# RXX-QDSB-SCH11-V1_00.net
KiCad netlist of a schematic drawn in Altium Designer
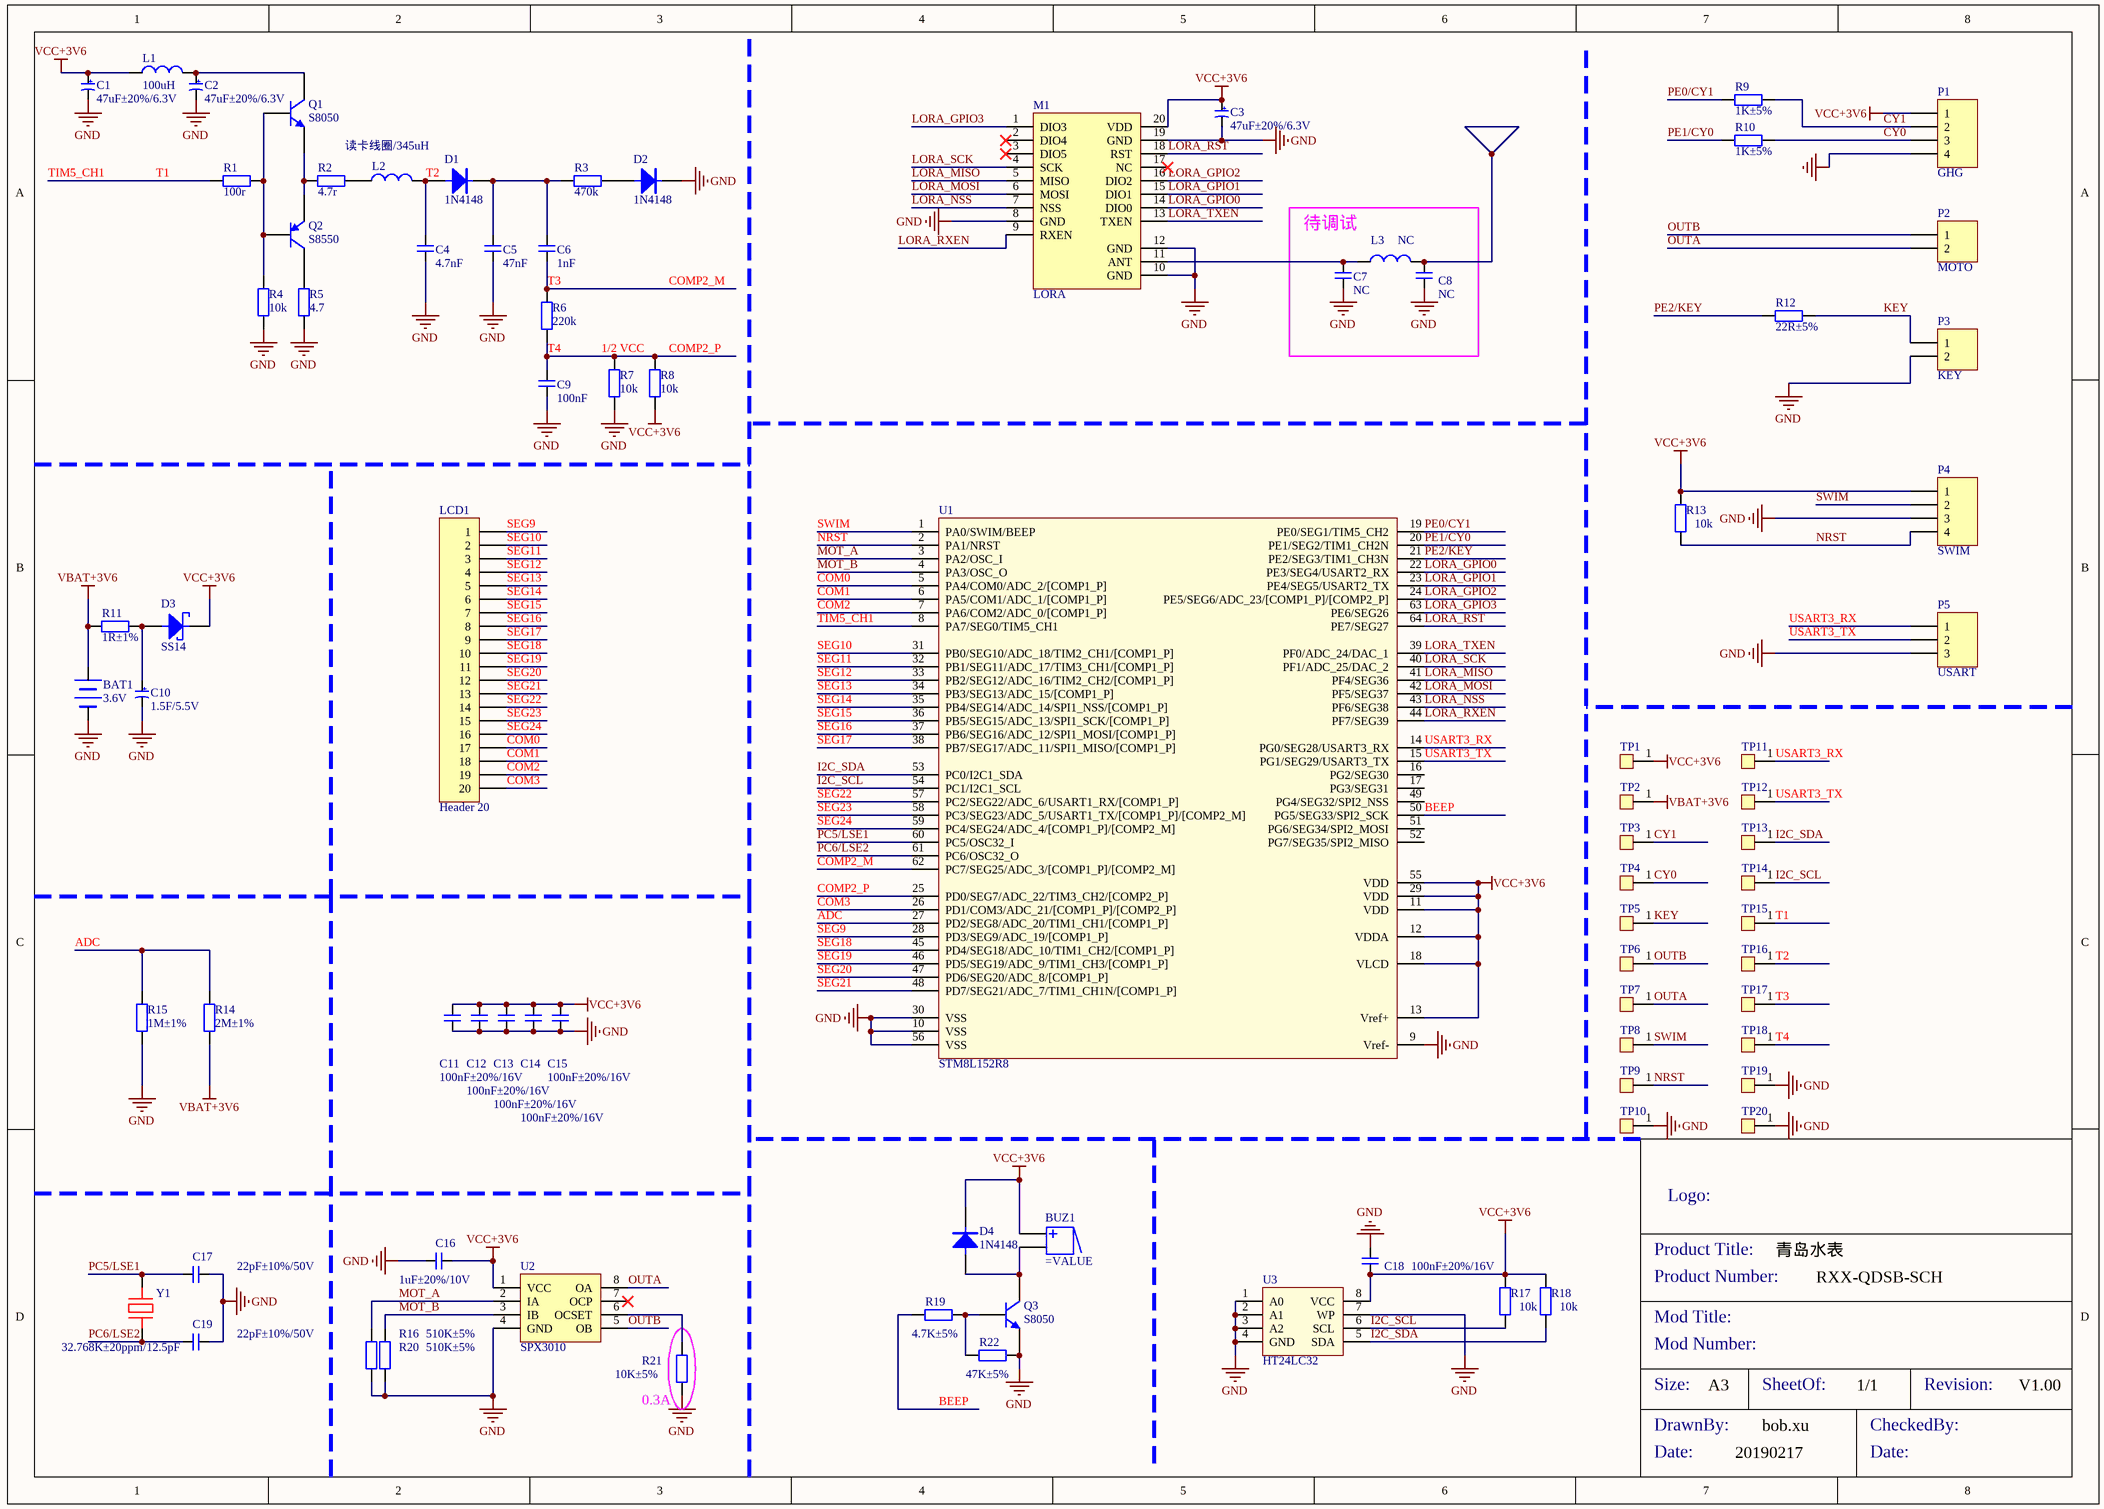
[diagram p0: RXX-QDSB-SCH11-V1.00.SchDoc]

(export (version "E")
  (design (tool "Eeschema 10.0.6"))
  (components
    (comp (ref "BAT1") (value "3.6V") (footprint "PH_2P_2R0_5R0X6R0_A") (libsource (lib "瑞臻信息") (part "BAT")))
    (comp (ref "BUZ1")
      (value "~")
      (footprint "DIP_BUZZER_2P_6R5_D12H9")
      (libsource (lib "瑞臻信息") (part "有源蜂鸣器"))
    )
    (comp (ref "C1")
      (value "47uF±20%/6.3V")
      (footprint "C3216+")
      (description "极性电容")
      (libsource (lib "瑞臻信息") (part "极性电容"))
    )
    (comp (ref "C2")
      (value "47uF±20%/6.3V")
      (footprint "C3216+")
      (description "极性电容")
      (libsource (lib "瑞臻信息") (part "极性电容"))
    )
    (comp (ref "C3")
      (value "47uF±20%/6.3V")
      (footprint "C3216+")
      (description "极性电容")
      (libsource (lib "瑞臻信息") (part "极性电容"))
    )
    (comp (ref "C4") (value "4.7nF") (description "无极性电容") (libsource (lib "瑞臻信息") (part "无极性电容")))
    (comp (ref "C5") (value "47nF") (description "无极性电容") (libsource (lib "瑞臻信息") (part "无极性电容")))
    (comp (ref "C6") (value "1nF") (description "无极性电容") (libsource (lib "瑞臻信息") (part "无极性电容")))
    (comp (ref "C7")
      (value "NC")
      (footprint "C0402")
      (description "无极性电容")
      (libsource (lib "瑞臻信息") (part "无极性电容"))
    )
    (comp (ref "C8")
      (value "NC")
      (footprint "C0402")
      (description "无极性电容")
      (libsource (lib "瑞臻信息") (part "无极性电容"))
    )
    (comp (ref "C9") (value "100nF") (description "无极性电容") (libsource (lib "瑞臻信息") (part "无极性电容")))
    (comp (ref "C10")
      (value "1.5F/5.5V")
      (footprint "CAP_2P_11R0_20X25H10_W")
      (description "极性电容")
      (libsource (lib "瑞臻信息") (part "极性电容"))
    )
    (comp (ref "C11")
      (value "100nF±20%/16V")
      (footprint "C0402")
      (description "无极性电容")
      (libsource (lib "瑞臻信息") (part "无极性电容"))
    )
    (comp (ref "C12")
      (value "100nF±20%/16V")
      (footprint "C0402")
      (description "无极性电容")
      (libsource (lib "瑞臻信息") (part "无极性电容"))
    )
    (comp (ref "C13")
      (value "100nF±20%/16V")
      (footprint "C0402")
      (description "无极性电容")
      (libsource (lib "瑞臻信息") (part "无极性电容"))
    )
    (comp (ref "C14")
      (value "100nF±20%/16V")
      (footprint "C0402")
      (description "无极性电容")
      (libsource (lib "瑞臻信息") (part "无极性电容"))
    )
    (comp (ref "C15")
      (value "100nF±20%/16V")
      (footprint "C0402")
      (description "无极性电容")
      (libsource (lib "瑞臻信息") (part "无极性电容"))
    )
    (comp (ref "C16")
      (value "1uF±20%/10V")
      (footprint "C0402")
      (description "无极性电容")
      (libsource (lib "瑞臻信息") (part "无极性电容"))
    )
    (comp (ref "C17")
      (value "22pF±10%/50V")
      (footprint "C0402")
      (description "无极性电容")
      (libsource (lib "瑞臻信息") (part "无极性电容"))
    )
    (comp (ref "C18")
      (value "100nF±20%/16V")
      (footprint "C0402")
      (description "无极性电容")
      (libsource (lib "瑞臻信息") (part "无极性电容"))
    )
    (comp (ref "C19")
      (value "22pF±10%/50V")
      (footprint "C0402")
      (description "无极性电容")
      (libsource (lib "瑞臻信息") (part "无极性电容"))
    )
    (comp (ref "D1") (value "1N4148") (description "普通二极管") (libsource (lib "瑞臻信息") (part "普通二极管")))
    (comp (ref "D2") (value "1N4148") (description "普通二极管") (libsource (lib "瑞臻信息") (part "普通二极管")))
    (comp (ref "D3")
      (value "SS14")
      (footprint "SMA_2P_2R8X4R6")
      (description "肖特基二极管")
      (libsource (lib "瑞臻信息") (part "肖特基二极管"))
    )
    (comp (ref "D4") (value "1N4148") (description "普通二极管") (libsource (lib "瑞臻信息") (part "普通二极管")))
    (comp (ref "L1") (value "100uH") (description "普通电感") (libsource (lib "瑞臻信息") (part "普通电感")))
    (comp (ref "L2") (value "读卡线圈/345uH") (description "普通电感") (libsource (lib "瑞臻信息") (part "普通电感")))
    (comp (ref "L3")
      (value "NC")
      (footprint "L0402")
      (description "普通电感")
      (libsource (lib "瑞臻信息") (part "普通电感"))
    )
    (comp (ref "LCD1")
      (value "Header 20")
      (footprint "HDR1X20")
      (description "Header, 20-Pin")
      (fields (field (name "PUBLISHER") "Altium Limited"))
      (libsource (lib "Miscellaneous Connectors") (part "Header 20"))
    )
    (comp (ref "M1") (value "LORA") (footprint "LORA_PIN_1") (libsource (lib "瑞臻信息") (part "LORA_PIN_1")))
    (comp (ref "P1")
      (value "GHG")
      (footprint "PH_4P_2R0_5R0X10R0_A")
      (description "Header, 4-Pin")
      (fields (field (name "PUBLISHER") "Altium Limited"))
      (libsource (lib "Miscellaneous Connectors") (part "Header 4"))
    )
    (comp (ref "P2")
      (value "MOTO")
      (footprint "PH_2P_2R0_5R0X6R0_A")
      (description "Header, 2-Pin")
      (fields (field (name "PUBLISHER") "Altium Limited"))
      (libsource (lib "Miscellaneous Connectors") (part "Header 2"))
    )
    (comp (ref "P3")
      (value "KEY")
      (footprint "PH_2P_2R0_5R0X6R0_A")
      (description "Header, 2-Pin")
      (fields (field (name "PUBLISHER") "Altium Limited"))
      (libsource (lib "Miscellaneous Connectors") (part "Header 2"))
    )
    (comp (ref "P4")
      (value "SWIM")
      (footprint "PH_4P_2R0_5R0X10R0_A")
      (description "Header, 4-Pin")
      (fields (field (name "PUBLISHER") "Altium Limited"))
      (libsource (lib "Miscellaneous Connectors") (part "Header 4"))
    )
    (comp (ref "P5")
      (value "USART")
      (footprint "PH_3P_2R0_5R0X8R0_A")
      (description "Header, 3-Pin")
      (fields (field (name "PUBLISHER") "Altium Limited"))
      (libsource (lib "Miscellaneous Connectors") (part "Header 3"))
    )
    (comp (ref "Q1") (value "S8050") (description "NPN三极管") (libsource (lib "瑞臻信息") (part "NPN三极管")))
    (comp (ref "Q2") (value "S8550") (description "PNP三极管") (libsource (lib "瑞臻信息") (part "PNP三极管")))
    (comp (ref "Q3")
      (value "S8050")
      (footprint "SOT23_3P_0R95_1R3X2R9")
      (description "NPN三极管")
      (libsource (lib "瑞臻信息") (part "NPN三极管"))
    )
    (comp (ref "R1") (value "100r") (description "普通电阻") (libsource (lib "") (part "普通电阻_3")))
    (comp (ref "R2") (value "4.7r") (description "普通电阻") (libsource (lib "") (part "普通电阻_3")))
    (comp (ref "R3") (value "470k") (description "普通电阻") (libsource (lib "") (part "普通电阻_3")))
    (comp (ref "R4") (value "10k") (description "普通电阻") (libsource (lib "") (part "普通电阻_2")))
    (comp (ref "R5") (value "4.7") (description "普通电阻") (libsource (lib "") (part "普通电阻_2")))
    (comp (ref "R6") (value "220k") (description "普通电阻") (libsource (lib "") (part "普通电阻_1")))
    (comp (ref "R7") (value "10k") (description "普通电阻") (libsource (lib "") (part "普通电阻_1")))
    (comp (ref "R8") (value "10k") (description "普通电阻") (libsource (lib "") (part "普通电阻_1")))
    (comp (ref "R9")
      (value "1K±5%")
      (footprint "R0402")
      (description "普通电阻")
      (libsource (lib "") (part "普通电阻_3"))
    )
    (comp (ref "R10")
      (value "1K±5%")
      (footprint "R0402")
      (description "普通电阻")
      (libsource (lib "") (part "普通电阻_3"))
    )
    (comp (ref "R11")
      (value "1R±1%")
      (footprint "R0805")
      (description "普通电阻")
      (libsource (lib "瑞臻信息") (part "普通电阻"))
    )
    (comp (ref "R12")
      (value "22R±5%")
      (footprint "R0402")
      (description "普通电阻")
      (libsource (lib "") (part "普通电阻_3"))
    )
    (comp (ref "R13")
      (value "10k")
      (footprint "R0402")
      (description "普通电阻")
      (libsource (lib "") (part "普通电阻_2"))
    )
    (comp (ref "R14")
      (value "2M±1%")
      (footprint "R0402")
      (description "普通电阻")
      (libsource (lib "") (part "普通电阻_1"))
    )
    (comp (ref "R15")
      (value "1M±1%")
      (footprint "R0402")
      (description "普通电阻")
      (libsource (lib "") (part "普通电阻_2"))
    )
    (comp (ref "R16")
      (value "510K±5%")
      (footprint "R0402")
      (description "普通电阻")
      (libsource (lib "") (part "普通电阻_2"))
    )
    (comp (ref "R17")
      (value "10k")
      (footprint "R0402")
      (description "普通电阻")
      (libsource (lib "") (part "普通电阻_2"))
    )
    (comp (ref "R18")
      (value "10k")
      (footprint "R0402")
      (description "普通电阻")
      (libsource (lib "") (part "普通电阻_2"))
    )
    (comp (ref "R19")
      (value "4.7K±5%")
      (footprint "R0402")
      (description "普通电阻")
      (libsource (lib "") (part "普通电阻_3"))
    )
    (comp (ref "R20")
      (value "510K±5%")
      (footprint "R0402")
      (description "普通电阻")
      (libsource (lib "") (part "普通电阻_2"))
    )
    (comp (ref "R21")
      (value "10K±5%")
      (footprint "R0402")
      (description "普通电阻")
      (libsource (lib "") (part "普通电阻_2"))
    )
    (comp (ref "R22")
      (value "47K±5%")
      (footprint "R0402")
      (description "普通电阻")
      (libsource (lib "瑞臻信息") (part "普通电阻"))
    )
    (comp (ref "TP1") (value "~") (description "测试点") (libsource (lib "瑞臻信息") (part "Test_Point")))
    (comp (ref "TP2") (value "~") (description "测试点") (libsource (lib "瑞臻信息") (part "Test_Point")))
    (comp (ref "TP3") (value "~") (description "测试点") (libsource (lib "瑞臻信息") (part "Test_Point")))
    (comp (ref "TP4") (value "~") (description "测试点") (libsource (lib "瑞臻信息") (part "Test_Point")))
    (comp (ref "TP5") (value "~") (description "测试点") (libsource (lib "瑞臻信息") (part "Test_Point")))
    (comp (ref "TP6") (value "~") (description "测试点") (libsource (lib "瑞臻信息") (part "Test_Point")))
    (comp (ref "TP7") (value "~") (description "测试点") (libsource (lib "瑞臻信息") (part "Test_Point")))
    (comp (ref "TP8") (value "~") (description "测试点") (libsource (lib "瑞臻信息") (part "Test_Point")))
    (comp (ref "TP9") (value "~") (description "测试点") (libsource (lib "瑞臻信息") (part "Test_Point")))
    (comp (ref "TP10") (value "~") (description "测试点") (libsource (lib "瑞臻信息") (part "Test_Point")))
    (comp (ref "TP11") (value "~") (description "测试点") (libsource (lib "瑞臻信息") (part "Test_Point")))
    (comp (ref "TP12") (value "~") (description "测试点") (libsource (lib "瑞臻信息") (part "Test_Point")))
    (comp (ref "TP13") (value "~") (description "测试点") (libsource (lib "瑞臻信息") (part "Test_Point")))
    (comp (ref "TP14") (value "~") (description "测试点") (libsource (lib "瑞臻信息") (part "Test_Point")))
    (comp (ref "TP15") (value "~") (description "测试点") (libsource (lib "瑞臻信息") (part "Test_Point")))
    (comp (ref "TP16") (value "~") (description "测试点") (libsource (lib "瑞臻信息") (part "Test_Point")))
    (comp (ref "TP17") (value "~") (description "测试点") (libsource (lib "瑞臻信息") (part "Test_Point")))
    (comp (ref "TP18") (value "~") (description "测试点") (libsource (lib "瑞臻信息") (part "Test_Point")))
    (comp (ref "TP19") (value "~") (description "测试点") (libsource (lib "瑞臻信息") (part "Test_Point")))
    (comp (ref "TP20") (value "~") (description "测试点") (libsource (lib "瑞臻信息") (part "Test_Point")))
    (comp (ref "U1") (value "STM8L152R8") (libsource (lib "瑞臻信息") (part "STM8L152R8")))
    (comp (ref "U2")
      (value "SPX3010")
      (footprint "SOP_8P_1R27_3R9X4R9")
      (libsource (lib "瑞臻信息") (part "SPX3010"))
    )
    (comp (ref "U3")
      (value "HT24LC32")
      (footprint "SOP_8P_1R27_3R9X4R9")
      (libsource (lib "瑞臻信息") (part "24CXX"))
    )
    (comp (ref "Y1")
      (value "32.768K±20ppm/12.5pF")
      (footprint "SMD_Crystal_2P_1R5X3R2")
      (description "两脚晶体谐振器")
      (libsource (lib "瑞臻信息") (part "两脚晶体谐振器"))
    )
  )
  (nets
    (net (code "1") (name "/1{slash}2 VCC") (class "Default")
      (node (ref "C9") (pin "1") (pinfunction "1_1") (pintype "passive"))
      (node (ref "R6") (pin "2") (pinfunction "2_2") (pintype "passive"))
      (node (ref "R7") (pin "1") (pinfunction "1_1") (pintype "passive"))
      (node (ref "R8") (pin "1") (pinfunction "1_1") (pintype "passive"))
      (node (ref "TP18") (pin "1") (pinfunction "1_1") (pintype "passive"))
      (node (ref "U1") (pin "25") (pinfunction "PD0/SEG7/ADC_22/TIM3_CH2/[COMP2_P]_25") (pintype "passive"))
    )
    (net (code "2") (name "/ADC") (class "Default")
      (node (ref "R14") (pin "1") (pinfunction "1_1") (pintype "passive"))
      (node (ref "R15") (pin "2") (pinfunction "2_2") (pintype "passive"))
      (node (ref "U1") (pin "27") (pinfunction "PD2/SEG8/ADC_20/TIM1_CH1/[COMP1_P]_27") (pintype "passive"))
    )
    (net (code "3") (name "/BEEP") (class "Default")
      (node (ref "R19") (pin "2") (pinfunction "2_2") (pintype "passive"))
      (node (ref "U1") (pin "50") (pinfunction "PG5/SEG33/SPI2_SCK_50") (pintype "passive"))
    )
    (net (code "4") (name "/COM0") (class "Default")
      (node (ref "LCD1") (pin "17") (pinfunction "17_17") (pintype "passive"))
      (node (ref "U1") (pin "5") (pinfunction "PA4/COM0/ADC_2/[COMP1_P]_5") (pintype "passive"))
    )
    (net (code "5") (name "/COM1") (class "Default")
      (node (ref "LCD1") (pin "18") (pinfunction "18_18") (pintype "passive"))
      (node (ref "U1") (pin "6") (pinfunction "PA5/COM1/ADC_1/[COMP1_P]_6") (pintype "passive"))
    )
    (net (code "6") (name "/COM2") (class "Default")
      (node (ref "LCD1") (pin "19") (pinfunction "19_19") (pintype "passive"))
      (node (ref "U1") (pin "7") (pinfunction "PA6/COM2/ADC_0/[COMP1_P]_7") (pintype "passive"))
    )
    (net (code "7") (name "/COM3") (class "Default")
      (node (ref "LCD1") (pin "20") (pinfunction "20_20") (pintype "passive"))
      (node (ref "U1") (pin "26") (pinfunction "PD1/COM3/ADC_21/[COMP1_P]/[COMP2_P]_26") (pintype "passive"))
    )
    (net (code "8") (name "/COMP2_M") (class "Default")
      (node (ref "C6") (pin "2") (pinfunction "2_2") (pintype "passive"))
      (node (ref "R6") (pin "1") (pinfunction "1_1") (pintype "passive"))
      (node (ref "TP17") (pin "1") (pinfunction "1_1") (pintype "passive"))
      (node (ref "U1") (pin "62") (pinfunction "PC7/SEG25/ADC_3/[COMP1_P]/[COMP2_M]_62") (pintype "passive"))
    )
    (net (code "9") (name "/CY0") (class "Default")
      (node (ref "P1") (pin "3") (pinfunction "3_3") (pintype "passive"))
      (node (ref "R10") (pin "1") (pinfunction "1_1") (pintype "passive"))
      (node (ref "TP4") (pin "1") (pinfunction "1_1") (pintype "passive"))
    )
    (net (code "10") (name "/CY1") (class "Default")
      (node (ref "P1") (pin "2") (pinfunction "2_2") (pintype "passive"))
      (node (ref "R9") (pin "1") (pinfunction "1_1") (pintype "passive"))
      (node (ref "TP3") (pin "1") (pinfunction "1_1") (pintype "passive"))
    )
    (net (code "11") (name "/I2C_SCL") (class "Default")
      (node (ref "R17") (pin "1") (pinfunction "1_1") (pintype "passive"))
      (node (ref "TP14") (pin "1") (pinfunction "1_1") (pintype "passive"))
      (node (ref "U1") (pin "54") (pinfunction "PC1/I2C1_SCL_54") (pintype "passive"))
      (node (ref "U3") (pin "6") (pinfunction "SCL_6") (pintype "passive"))
    )
    (net (code "12") (name "/I2C_SDA") (class "Default")
      (node (ref "R18") (pin "1") (pinfunction "1_1") (pintype "passive"))
      (node (ref "TP13") (pin "1") (pinfunction "1_1") (pintype "passive"))
      (node (ref "U1") (pin "53") (pinfunction "PC0/I2C1_SDA_53") (pintype "passive"))
      (node (ref "U3") (pin "5") (pinfunction "SDA_5") (pintype "passive"))
    )
    (net (code "13") (name "/KEY") (class "Default")
      (node (ref "P3") (pin "1") (pinfunction "1_1") (pintype "passive"))
      (node (ref "R12") (pin "1") (pinfunction "1_1") (pintype "passive"))
      (node (ref "TP5") (pin "1") (pinfunction "1_1") (pintype "passive"))
    )
    (net (code "14") (name "/LORA_GPIO0") (class "Default")
      (node (ref "M1") (pin "14") (pinfunction "DIO0_14") (pintype "passive"))
      (node (ref "U1") (pin "22") (pinfunction "PE3/SEG4/USART2_RX_22") (pintype "passive"))
    )
    (net (code "15") (name "/LORA_GPIO1") (class "Default")
      (node (ref "M1") (pin "15") (pinfunction "DIO1_15") (pintype "passive"))
      (node (ref "U1") (pin "23") (pinfunction "PE4/SEG5/USART2_TX_23") (pintype "passive"))
    )
    (net (code "16") (name "/LORA_GPIO2") (class "Default")
      (node (ref "M1") (pin "16") (pinfunction "DIO2_16") (pintype "passive"))
      (node (ref "U1") (pin "24") (pinfunction "PE5/SEG6/ADC_23/[COMP1_P]/[COMP2_P]_24") (pintype "passive"))
    )
    (net (code "17") (name "/LORA_GPIO3") (class "Default")
      (node (ref "M1") (pin "1") (pinfunction "DIO3_1") (pintype "passive"))
      (node (ref "U1") (pin "63") (pinfunction "PE6/SEG26_63") (pintype "passive"))
    )
    (net (code "18") (name "/LORA_MISO") (class "Default")
      (node (ref "M1") (pin "5") (pinfunction "MISO_5") (pintype "passive"))
      (node (ref "U1") (pin "41") (pinfunction "PF4/SEG36_41") (pintype "passive"))
    )
    (net (code "19") (name "/LORA_MOSI") (class "Default")
      (node (ref "M1") (pin "6") (pinfunction "MOSI_6") (pintype "passive"))
      (node (ref "U1") (pin "42") (pinfunction "PF5/SEG37_42") (pintype "passive"))
    )
    (net (code "20") (name "/LORA_NSS") (class "Default")
      (node (ref "M1") (pin "7") (pinfunction "NSS_7") (pintype "passive"))
      (node (ref "U1") (pin "43") (pinfunction "PF6/SEG38_43") (pintype "passive"))
    )
    (net (code "21") (name "/LORA_RST") (class "Default")
      (node (ref "M1") (pin "18") (pinfunction "RST_18") (pintype "passive"))
      (node (ref "U1") (pin "64") (pinfunction "PE7/SEG27_64") (pintype "passive"))
    )
    (net (code "22") (name "/LORA_RXEN") (class "Default")
      (node (ref "M1") (pin "9") (pinfunction "RXEN_9") (pintype "passive"))
      (node (ref "U1") (pin "44") (pinfunction "PF7/SEG39_44") (pintype "passive"))
    )
    (net (code "23") (name "/LORA_SCK") (class "Default")
      (node (ref "M1") (pin "4") (pinfunction "SCK_4") (pintype "passive"))
      (node (ref "U1") (pin "40") (pinfunction "PF1/ADC_25/DAC_2_40") (pintype "passive"))
    )
    (net (code "24") (name "/LORA_TXEN") (class "Default")
      (node (ref "M1") (pin "13") (pinfunction "TXEN_13") (pintype "passive"))
      (node (ref "U1") (pin "39") (pinfunction "PF0/ADC_24/DAC_1_39") (pintype "passive"))
    )
    (net (code "25") (name "/MOT_A") (class "Default")
      (node (ref "R16") (pin "2") (pinfunction "2_2") (pintype "passive"))
      (node (ref "U1") (pin "3") (pinfunction "PA2/OSC_I_3") (pintype "passive"))
      (node (ref "U2") (pin "2") (pinfunction "IA_2") (pintype "passive"))
    )
    (net (code "26") (name "/MOT_B") (class "Default")
      (node (ref "R20") (pin "2") (pinfunction "2_2") (pintype "passive"))
      (node (ref "U1") (pin "4") (pinfunction "PA3/OSC_O_4") (pintype "passive"))
      (node (ref "U2") (pin "3") (pinfunction "IB_3") (pintype "passive"))
    )
    (net (code "27") (name "/NRST") (class "Default")
      (node (ref "P4") (pin "4") (pinfunction "4_4") (pintype "passive"))
      (node (ref "R13") (pin "1") (pinfunction "1_1") (pintype "passive"))
      (node (ref "TP9") (pin "1") (pinfunction "1_1") (pintype "passive"))
      (node (ref "U1") (pin "2") (pinfunction "PA1/NRST_2") (pintype "passive"))
    )
    (net (code "28") (name "/OUTA") (class "Default")
      (node (ref "P2") (pin "2") (pinfunction "2_2") (pintype "passive"))
      (node (ref "TP7") (pin "1") (pinfunction "1_1") (pintype "passive"))
      (node (ref "U2") (pin "8") (pinfunction "OA_8") (pintype "passive"))
    )
    (net (code "29") (name "/OUTB") (class "Default")
      (node (ref "P2") (pin "1") (pinfunction "1_1") (pintype "passive"))
      (node (ref "TP6") (pin "1") (pinfunction "1_1") (pintype "passive"))
      (node (ref "U2") (pin "5") (pinfunction "OB_5") (pintype "passive"))
    )
    (net (code "30") (name "/PC5{slash}LSE1") (class "Default")
      (node (ref "C17") (pin "2") (pinfunction "2_2") (pintype "passive"))
      (node (ref "U1") (pin "60") (pinfunction "PC5/OSC32_I_60") (pintype "passive"))
      (node (ref "Y1") (pin "2") (pinfunction "2_2") (pintype "passive"))
    )
    (net (code "31") (name "/PC6{slash}LSE2") (class "Default")
      (node (ref "C19") (pin "2") (pinfunction "2_2") (pintype "passive"))
      (node (ref "U1") (pin "61") (pinfunction "PC6/OSC32_O_61") (pintype "passive"))
      (node (ref "Y1") (pin "1") (pinfunction "1_1") (pintype "passive"))
    )
    (net (code "32") (name "/PE0{slash}CY1") (class "Default")
      (node (ref "R9") (pin "2") (pinfunction "2_2") (pintype "passive"))
      (node (ref "U1") (pin "19") (pinfunction "PE0/SEG1/TIM5_CH2_19") (pintype "passive"))
    )
    (net (code "33") (name "/PE1{slash}CY0") (class "Default")
      (node (ref "R10") (pin "2") (pinfunction "2_2") (pintype "passive"))
      (node (ref "U1") (pin "20") (pinfunction "PE1/SEG2/TIM1_CH2N_20") (pintype "passive"))
    )
    (net (code "34") (name "/PE2{slash}KEY") (class "Default")
      (node (ref "R12") (pin "2") (pinfunction "2_2") (pintype "passive"))
      (node (ref "U1") (pin "21") (pinfunction "PE2/SEG3/TIM1_CH3N_21") (pintype "passive"))
    )
    (net (code "35") (name "/SEG9") (class "Default")
      (node (ref "LCD1") (pin "1") (pinfunction "1_1") (pintype "passive"))
      (node (ref "U1") (pin "28") (pinfunction "PD3/SEG9/ADC_19/[COMP1_P]_28") (pintype "passive"))
    )
    (net (code "36") (name "/SEG10") (class "Default")
      (node (ref "LCD1") (pin "2") (pinfunction "2_2") (pintype "passive"))
      (node (ref "U1") (pin "31") (pinfunction "PB0/SEG10/ADC_18/TIM2_CH1/[COMP1_P]_31") (pintype "passive"))
    )
    (net (code "37") (name "/SEG11") (class "Default")
      (node (ref "LCD1") (pin "3") (pinfunction "3_3") (pintype "passive"))
      (node (ref "U1") (pin "32") (pinfunction "PB1/SEG11/ADC_17/TIM3_CH1/[COMP1_P]_32") (pintype "passive"))
    )
    (net (code "38") (name "/SEG12") (class "Default")
      (node (ref "LCD1") (pin "4") (pinfunction "4_4") (pintype "passive"))
      (node (ref "U1") (pin "33") (pinfunction "PB2/SEG12/ADC_16/TIM2_CH2/[COMP1_P]_33") (pintype "passive"))
    )
    (net (code "39") (name "/SEG13") (class "Default")
      (node (ref "LCD1") (pin "5") (pinfunction "5_5") (pintype "passive"))
      (node (ref "U1") (pin "34") (pinfunction "PB3/SEG13/ADC_15/[COMP1_P]_34") (pintype "passive"))
    )
    (net (code "40") (name "/SEG14") (class "Default")
      (node (ref "LCD1") (pin "6") (pinfunction "6_6") (pintype "passive"))
      (node (ref "U1") (pin "35") (pinfunction "PB4/SEG14/ADC_14/SPI1_NSS/[COMP1_P]_35") (pintype "passive"))
    )
    (net (code "41") (name "/SEG15") (class "Default")
      (node (ref "LCD1") (pin "7") (pinfunction "7_7") (pintype "passive"))
      (node (ref "U1") (pin "36") (pinfunction "PB5/SEG15/ADC_13/SPI1_SCK/[COMP1_P]_36") (pintype "passive"))
    )
    (net (code "42") (name "/SEG16") (class "Default")
      (node (ref "LCD1") (pin "8") (pinfunction "8_8") (pintype "passive"))
      (node (ref "U1") (pin "37") (pinfunction "PB6/SEG16/ADC_12/SPI1_MOSI/[COMP1_P]_37") (pintype "passive"))
    )
    (net (code "43") (name "/SEG17") (class "Default")
      (node (ref "LCD1") (pin "9") (pinfunction "9_9") (pintype "passive"))
      (node (ref "U1") (pin "38") (pinfunction "PB7/SEG17/ADC_11/SPI1_MISO/[COMP1_P]_38") (pintype "passive"))
    )
    (net (code "44") (name "/SEG18") (class "Default")
      (node (ref "LCD1") (pin "10") (pinfunction "10_10") (pintype "passive"))
      (node (ref "U1") (pin "45") (pinfunction "PD4/SEG18/ADC_10/TIM1_CH2/[COMP1_P]_45") (pintype "passive"))
    )
    (net (code "45") (name "/SEG19") (class "Default")
      (node (ref "LCD1") (pin "11") (pinfunction "11_11") (pintype "passive"))
      (node (ref "U1") (pin "46") (pinfunction "PD5/SEG19/ADC_9/TIM1_CH3/[COMP1_P]_46") (pintype "passive"))
    )
    (net (code "46") (name "/SEG20") (class "Default")
      (node (ref "LCD1") (pin "12") (pinfunction "12_12") (pintype "passive"))
      (node (ref "U1") (pin "47") (pinfunction "PD6/SEG20/ADC_8/[COMP1_P]_47") (pintype "passive"))
    )
    (net (code "47") (name "/SEG21") (class "Default")
      (node (ref "LCD1") (pin "13") (pinfunction "13_13") (pintype "passive"))
      (node (ref "U1") (pin "48") (pinfunction "PD7/SEG21/ADC_7/TIM1_CH1N/[COMP1_P]_48") (pintype "passive"))
    )
    (net (code "48") (name "/SEG22") (class "Default")
      (node (ref "LCD1") (pin "14") (pinfunction "14_14") (pintype "passive"))
      (node (ref "U1") (pin "57") (pinfunction "PC2/SEG22/ADC_6/USART1_RX/[COMP1_P]_57") (pintype "passive"))
    )
    (net (code "49") (name "/SEG23") (class "Default")
      (node (ref "LCD1") (pin "15") (pinfunction "15_15") (pintype "passive"))
      (node (ref "U1") (pin "58") (pinfunction "PC3/SEG23/ADC_5/USART1_TX/[COMP1_P]/[COMP2_M]_58") (pintype "passive"))
    )
    (net (code "50") (name "/SEG24") (class "Default")
      (node (ref "LCD1") (pin "16") (pinfunction "16_16") (pintype "passive"))
      (node (ref "U1") (pin "59") (pinfunction "PC4/SEG24/ADC_4/[COMP1_P]/[COMP2_M]_59") (pintype "passive"))
    )
    (net (code "51") (name "/SWIM") (class "Default")
      (node (ref "P4") (pin "2") (pinfunction "2_2") (pintype "passive"))
      (node (ref "TP8") (pin "1") (pinfunction "1_1") (pintype "passive"))
      (node (ref "U1") (pin "1") (pinfunction "PA0/SWIM/BEEP_1") (pintype "passive"))
    )
    (net (code "52") (name "/T1") (class "Default")
      (node (ref "R1") (pin "2") (pinfunction "2_2") (pintype "passive"))
      (node (ref "TP15") (pin "1") (pinfunction "1_1") (pintype "passive"))
      (node (ref "U1") (pin "8") (pinfunction "PA7/SEG0/TIM5_CH1_8") (pintype "passive"))
    )
    (net (code "53") (name "/T2") (class "Default")
      (node (ref "C4") (pin "1") (pinfunction "1_1") (pintype "passive"))
      (node (ref "D1") (pin "1") (pinfunction "A_1") (pintype "passive"))
      (node (ref "L2") (pin "2") (pinfunction "2_2") (pintype "passive"))
      (node (ref "TP16") (pin "1") (pinfunction "1_1") (pintype "passive"))
    )
    (net (code "54") (name "/USART3_RX") (class "Default")
      (node (ref "P5") (pin "1") (pinfunction "1_1") (pintype "passive"))
      (node (ref "TP11") (pin "1") (pinfunction "1_1") (pintype "passive"))
      (node (ref "U1") (pin "14") (pinfunction "PG0/SEG28/USART3_RX_14") (pintype "passive"))
    )
    (net (code "55") (name "/USART3_TX") (class "Default")
      (node (ref "P5") (pin "2") (pinfunction "2_2") (pintype "passive"))
      (node (ref "TP12") (pin "1") (pinfunction "1_1") (pintype "passive"))
      (node (ref "U1") (pin "15") (pinfunction "PG1/SEG29/USART3_TX_15") (pintype "passive"))
    )
    (net (code "56") (name "GND") (class "Default")
      (node (ref "BAT1") (pin "2") (pintype "passive"))
      (node (ref "C1") (pin "2") (pinfunction "2_2") (pintype "passive"))
      (node (ref "C10") (pin "2") (pinfunction "2_2") (pintype "passive"))
      (node (ref "C11") (pin "2") (pinfunction "2_2") (pintype "passive"))
      (node (ref "C12") (pin "2") (pinfunction "2_2") (pintype "passive"))
      (node (ref "C13") (pin "2") (pinfunction "2_2") (pintype "passive"))
      (node (ref "C14") (pin "2") (pinfunction "2_2") (pintype "passive"))
      (node (ref "C15") (pin "2") (pinfunction "2_2") (pintype "passive"))
      (node (ref "C16") (pin "2") (pinfunction "2_2") (pintype "passive"))
      (node (ref "C17") (pin "1") (pinfunction "1_1") (pintype "passive"))
      (node (ref "C18") (pin "1") (pinfunction "1_1") (pintype "passive"))
      (node (ref "C19") (pin "1") (pinfunction "1_1") (pintype "passive"))
      (node (ref "C2") (pin "2") (pinfunction "2_2") (pintype "passive"))
      (node (ref "C3") (pin "2") (pinfunction "2_2") (pintype "passive"))
      (node (ref "C4") (pin "2") (pinfunction "2_2") (pintype "passive"))
      (node (ref "C5") (pin "2") (pinfunction "2_2") (pintype "passive"))
      (node (ref "C7") (pin "2") (pinfunction "2_2") (pintype "passive"))
      (node (ref "C8") (pin "2") (pinfunction "2_2") (pintype "passive"))
      (node (ref "C9") (pin "2") (pinfunction "2_2") (pintype "passive"))
      (node (ref "D2") (pin "2") (pinfunction "K_2") (pintype "passive"))
      (node (ref "M1") (pin "10") (pinfunction "GND_10") (pintype "passive"))
      (node (ref "M1") (pin "12") (pinfunction "GND_12") (pintype "passive"))
      (node (ref "M1") (pin "19") (pinfunction "GND_19") (pintype "passive"))
      (node (ref "M1") (pin "8") (pinfunction "GND_8") (pintype "passive"))
      (node (ref "P1") (pin "4") (pinfunction "4_4") (pintype "passive"))
      (node (ref "P3") (pin "2") (pinfunction "2_2") (pintype "passive"))
      (node (ref "P4") (pin "3") (pinfunction "3_3") (pintype "passive"))
      (node (ref "P5") (pin "3") (pinfunction "3_3") (pintype "passive"))
      (node (ref "Q3") (pin "2") (pinfunction "E_2") (pintype "passive"))
      (node (ref "R15") (pin "1") (pinfunction "1_1") (pintype "passive"))
      (node (ref "R16") (pin "1") (pinfunction "1_1") (pintype "passive"))
      (node (ref "R20") (pin "1") (pinfunction "1_1") (pintype "passive"))
      (node (ref "R21") (pin "1") (pinfunction "1_1") (pintype "passive"))
      (node (ref "R22") (pin "2") (pinfunction "2_2") (pintype "passive"))
      (node (ref "R4") (pin "1") (pinfunction "1_1") (pintype "passive"))
      (node (ref "R5") (pin "1") (pinfunction "1_1") (pintype "passive"))
      (node (ref "R7") (pin "2") (pinfunction "2_2") (pintype "passive"))
      (node (ref "TP10") (pin "1") (pinfunction "1_1") (pintype "passive"))
      (node (ref "TP19") (pin "1") (pinfunction "1_1") (pintype "passive"))
      (node (ref "TP20") (pin "1") (pinfunction "1_1") (pintype "passive"))
      (node (ref "U1") (pin "10") (pinfunction "VSS_10") (pintype "passive"))
      (node (ref "U1") (pin "30") (pinfunction "VSS_30") (pintype "passive"))
      (node (ref "U1") (pin "56") (pinfunction "VSS_56") (pintype "passive"))
      (node (ref "U1") (pin "9") (pinfunction "Vref-_9") (pintype "passive"))
      (node (ref "U2") (pin "4") (pinfunction "GND_4") (pintype "passive"))
      (node (ref "U3") (pin "1") (pinfunction "A0_1") (pintype "passive"))
      (node (ref "U3") (pin "2") (pinfunction "A1_2") (pintype "passive"))
      (node (ref "U3") (pin "3") (pinfunction "A2_3") (pintype "passive"))
      (node (ref "U3") (pin "4") (pinfunction "GND_4") (pintype "passive"))
      (node (ref "U3") (pin "7") (pinfunction "WP_7") (pintype "passive"))
    )
    (net (code "57") (name "Net-(C8-Pad1)") (class "Default")
      (node (ref "C8") (pin "1") (pinfunction "1_1") (pintype "passive"))
      (node (ref "L3") (pin "2") (pinfunction "2_2") (pintype "passive"))
    )
    (net (code "58") (name "Net-(D1-K)") (class "Default")
      (node (ref "C5") (pin "1") (pinfunction "1_1") (pintype "passive"))
      (node (ref "C6") (pin "1") (pinfunction "1_1") (pintype "passive"))
      (node (ref "D1") (pin "2") (pinfunction "K_2") (pintype "passive"))
      (node (ref "R3") (pin "2") (pinfunction "2_2") (pintype "passive"))
    )
    (net (code "59") (name "Net-(D2-A)") (class "Default")
      (node (ref "D2") (pin "1") (pinfunction "A_1") (pintype "passive"))
      (node (ref "R3") (pin "1") (pinfunction "1_1") (pintype "passive"))
    )
    (net (code "60") (name "Net-(D3-A)") (class "Default")
      (node (ref "C10") (pin "1") (pinfunction "1_1") (pintype "passive"))
      (node (ref "D3") (pin "1") (pinfunction "A_1") (pintype "passive"))
      (node (ref "R11") (pin "2") (pinfunction "2_2") (pintype "passive"))
    )
    (net (code "61") (name "Net-(D4-A)") (class "Default")
      (node (ref "BUZ1") (pin "2") (pinfunction "2_2") (pintype "passive"))
      (node (ref "D4") (pin "1") (pinfunction "A_1") (pintype "passive"))
      (node (ref "Q3") (pin "3") (pinfunction "C_3") (pintype "passive"))
    )
    (net (code "62") (name "Net-(L2-Pad1)") (class "Default")
      (node (ref "L2") (pin "1") (pinfunction "1_1") (pintype "passive"))
      (node (ref "R2") (pin "1") (pinfunction "1_1") (pintype "passive"))
    )
    (net (code "63") (name "Net-(M1-ANT)") (class "Default")
      (node (ref "C7") (pin "1") (pinfunction "1_1") (pintype "passive"))
      (node (ref "L3") (pin "1") (pinfunction "1_1") (pintype "passive"))
      (node (ref "M1") (pin "11") (pinfunction "ANT_11") (pintype "passive"))
    )
    (net (code "64") (name "Net-(Q1-B)") (class "Default")
      (node (ref "Q1") (pin "1") (pinfunction "B_1") (pintype "passive"))
      (node (ref "Q2") (pin "1") (pinfunction "B_1") (pintype "passive"))
      (node (ref "R1") (pin "1") (pinfunction "1_1") (pintype "passive"))
      (node (ref "R4") (pin "2") (pinfunction "2_2") (pintype "passive"))
    )
    (net (code "65") (name "Net-(Q1-C)") (class "Default")
      (node (ref "C2") (pin "1") (pinfunction "1_1") (pintype "passive"))
      (node (ref "L1") (pin "2") (pinfunction "2_2") (pintype "passive"))
      (node (ref "Q1") (pin "3") (pinfunction "C_3") (pintype "passive"))
    )
    (net (code "66") (name "Net-(Q1-E)") (class "Default")
      (node (ref "Q1") (pin "2") (pinfunction "E_2") (pintype "passive"))
      (node (ref "Q2") (pin "2") (pinfunction "E_2") (pintype "passive"))
      (node (ref "R2") (pin "2") (pinfunction "2_2") (pintype "passive"))
    )
    (net (code "67") (name "Net-(Q2-C)") (class "Default")
      (node (ref "Q2") (pin "3") (pinfunction "C_3") (pintype "passive"))
      (node (ref "R5") (pin "2") (pinfunction "2_2") (pintype "passive"))
    )
    (net (code "68") (name "Net-(Q3-B)") (class "Default")
      (node (ref "Q3") (pin "1") (pinfunction "B_1") (pintype "passive"))
      (node (ref "R19") (pin "1") (pinfunction "1_1") (pintype "passive"))
      (node (ref "R22") (pin "1") (pinfunction "1_1") (pintype "passive"))
    )
    (net (code "69") (name "Net-(U2-OCSET)") (class "Default")
      (node (ref "R21") (pin "2") (pinfunction "2_2") (pintype "passive"))
      (node (ref "U2") (pin "6") (pinfunction "OCSET_6") (pintype "passive"))
    )
    (net (code "70") (name "VBAT+3V6") (class "Default")
      (node (ref "BAT1") (pin "1") (pintype "passive"))
      (node (ref "R11") (pin "1") (pinfunction "1_1") (pintype "passive"))
      (node (ref "R14") (pin "2") (pinfunction "2_2") (pintype "passive"))
      (node (ref "TP2") (pin "1") (pinfunction "1_1") (pintype "passive"))
    )
    (net (code "71") (name "VCC+3V6") (class "Default")
      (node (ref "BUZ1") (pin "1") (pinfunction "1_1") (pintype "passive"))
      (node (ref "C1") (pin "1") (pinfunction "1_1") (pintype "passive"))
      (node (ref "C11") (pin "1") (pinfunction "1_1") (pintype "passive"))
      (node (ref "C12") (pin "1") (pinfunction "1_1") (pintype "passive"))
      (node (ref "C13") (pin "1") (pinfunction "1_1") (pintype "passive"))
      (node (ref "C14") (pin "1") (pinfunction "1_1") (pintype "passive"))
      (node (ref "C15") (pin "1") (pinfunction "1_1") (pintype "passive"))
      (node (ref "C16") (pin "1") (pinfunction "1_1") (pintype "passive"))
      (node (ref "C18") (pin "2") (pinfunction "2_2") (pintype "passive"))
      (node (ref "C3") (pin "1") (pinfunction "1_1") (pintype "passive"))
      (node (ref "D3") (pin "2") (pinfunction "K_2") (pintype "passive"))
      (node (ref "D4") (pin "2") (pinfunction "K_2") (pintype "passive"))
      (node (ref "L1") (pin "1") (pinfunction "1_1") (pintype "passive"))
      (node (ref "M1") (pin "20") (pinfunction "VDD_20") (pintype "passive"))
      (node (ref "P1") (pin "1") (pinfunction "1_1") (pintype "passive"))
      (node (ref "P4") (pin "1") (pinfunction "1_1") (pintype "passive"))
      (node (ref "R13") (pin "2") (pinfunction "2_2") (pintype "passive"))
      (node (ref "R17") (pin "2") (pinfunction "2_2") (pintype "passive"))
      (node (ref "R18") (pin "2") (pinfunction "2_2") (pintype "passive"))
      (node (ref "R8") (pin "2") (pinfunction "2_2") (pintype "passive"))
      (node (ref "TP1") (pin "1") (pinfunction "1_1") (pintype "passive"))
      (node (ref "U1") (pin "11") (pinfunction "VDD_11") (pintype "passive"))
      (node (ref "U1") (pin "12") (pinfunction "VDDA_12") (pintype "passive"))
      (node (ref "U1") (pin "13") (pinfunction "Vref+_13") (pintype "passive"))
      (node (ref "U1") (pin "18") (pinfunction "VLCD_18") (pintype "passive"))
      (node (ref "U1") (pin "29") (pinfunction "VDD_29") (pintype "passive"))
      (node (ref "U1") (pin "55") (pinfunction "VDD_55") (pintype "passive"))
      (node (ref "U2") (pin "1") (pinfunction "VCC_1") (pintype "passive"))
      (node (ref "U3") (pin "8") (pinfunction "VCC_8") (pintype "passive"))
    )
    (net (code "72") (name "unconnected-(M1-DIO4-Pad2)") (class "Default")
      (node (ref "M1") (pin "2") (pinfunction "DIO4_2") (pintype "passive+no_connect"))
    )
    (net (code "73") (name "unconnected-(M1-DIO5-Pad3)") (class "Default")
      (node (ref "M1") (pin "3") (pinfunction "DIO5_3") (pintype "passive+no_connect"))
    )
    (net (code "74") (name "unconnected-(M1-NC-Pad17)") (class "Default")
      (node (ref "M1") (pin "17") (pinfunction "NC_17") (pintype "passive+no_connect"))
    )
    (net (code "75") (name "unconnected-(U1-PG2{slash}SEG30-Pad16)") (class "Default")
      (node (ref "U1") (pin "16") (pinfunction "PG2/SEG30_16") (pintype "passive"))
    )
    (net (code "76") (name "unconnected-(U1-PG3{slash}SEG31-Pad17)") (class "Default")
      (node (ref "U1") (pin "17") (pinfunction "PG3/SEG31_17") (pintype "passive"))
    )
    (net (code "77") (name "unconnected-(U1-PG4{slash}SEG32{slash}SPI2_NSS-Pad49)") (class "Default")
      (node (ref "U1") (pin "49") (pinfunction "PG4/SEG32/SPI2_NSS_49") (pintype "passive"))
    )
    (net (code "78") (name "unconnected-(U1-PG6{slash}SEG34{slash}SPI2_MOSI-Pad51)") (class "Default")
      (node (ref "U1") (pin "51") (pinfunction "PG6/SEG34/SPI2_MOSI_51") (pintype "passive"))
    )
    (net (code "79") (name "unconnected-(U1-PG7{slash}SEG35{slash}SPI2_MISO-Pad52)") (class "Default")
      (node (ref "U1") (pin "52") (pinfunction "PG7/SEG35/SPI2_MISO_52") (pintype "passive"))
    )
    (net (code "80") (name "unconnected-(U2-OCP-Pad7)") (class "Default")
      (node (ref "U2") (pin "7") (pinfunction "OCP_7") (pintype "passive+no_connect"))
    )
  )
)
